# TX_test.net
KiCad netlist of a schematic drawn in EAGLE
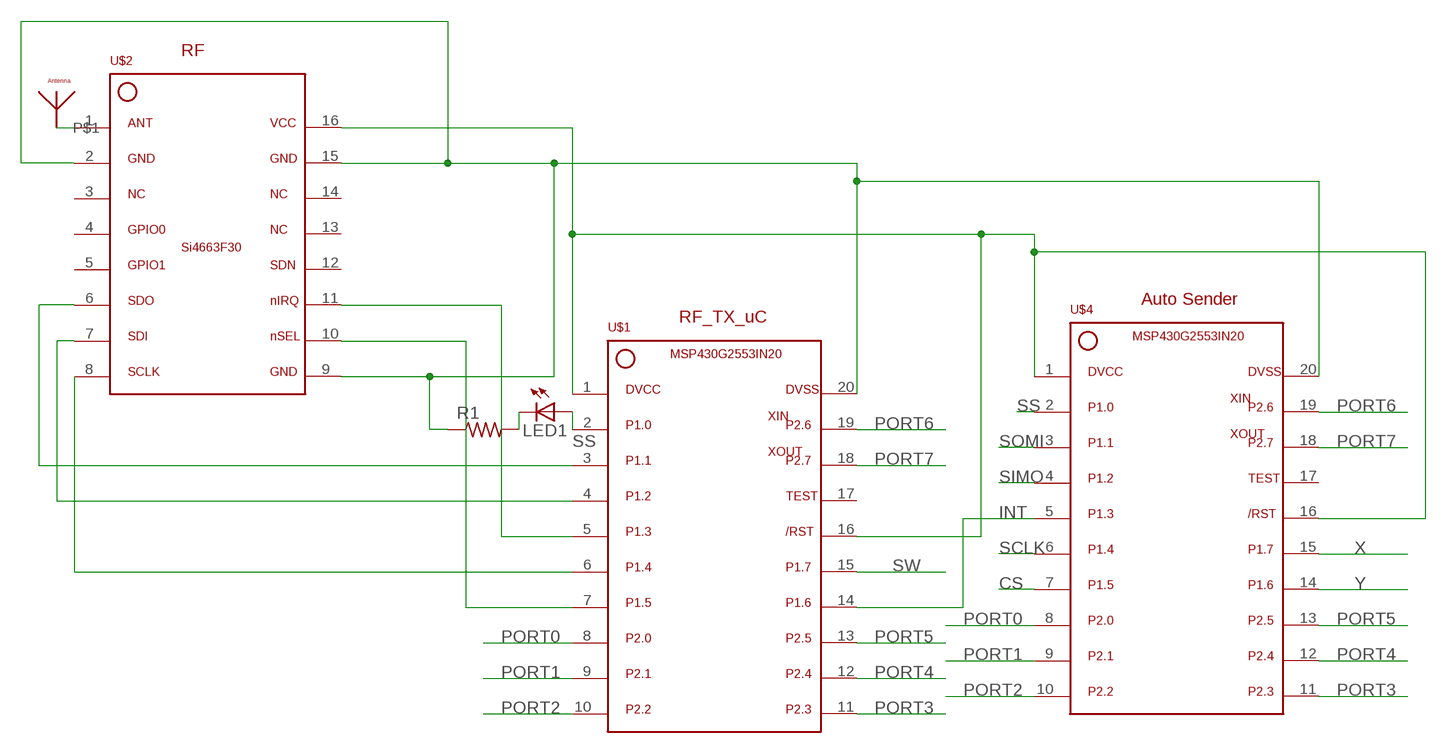
[diagram p0: schematic, sheet 1]

(export (version "E")
  (design (tool "Eeschema 10.0.6"))
  (components
    (comp (ref "LED1")
      (value "LED3MM")
      (footprint "eagle-import:LED3MM")
      (libsource (lib "eagle-import") (part "LED3MM"))
    )
    (comp (ref "R1")
      (value "R-US_0204/7")
      (footprint "eagle-import:0204_7")
      (libsource (lib "eagle-import") (part "R-US_0204/7"))
    )
    (comp (ref "U$1")
      (value "MSP430G2553IN20")
      (footprint "eagle-import:DIP762W53P254L2215H508Q20B")
      (libsource (lib "eagle-import") (part "MSP430G2553IN20"))
    )
    (comp (ref "U$2")
      (value "SI4663F30SI4663F30-3D")
      (footprint "eagle-import:INDCAV400P3800X2000X400-16N")
      (libsource (lib "eagle-import") (part "SI4663F30SI4663F30-3D"))
    )
    (comp (ref "U$3")
      (value "ANTENNA")
      (footprint "eagle-import:ANTENNA")
      (libsource (lib "eagle-import") (part "ANTENNA"))
    )
    (comp (ref "U$4")
      (value "MSP430G2553IN20")
      (footprint "eagle-import:DIP762W53P254L2215H508Q20B")
      (libsource (lib "eagle-import") (part "MSP430G2553IN20"))
    )
  )
  (nets
    (net (code "1") (name "/CS") (class "Default")
      (node (ref "U$4") (pin "7") (pinfunction "P$7_7") (pintype "bidirectional"))
    )
    (net (code "2") (name "/INT") (class "Default")
      (node (ref "U$1") (pin "14") (pinfunction "P$14_14") (pintype "bidirectional"))
      (node (ref "U$4") (pin "5") (pinfunction "P$5_5") (pintype "bidirectional"))
    )
    (net (code "3") (name "/PORT0") (class "Default")
      (node (ref "U$1") (pin "8") (pinfunction "P$8_8") (pintype "bidirectional"))
      (node (ref "U$4") (pin "8") (pinfunction "P$8_8") (pintype "bidirectional"))
    )
    (net (code "4") (name "/PORT1") (class "Default")
      (node (ref "U$1") (pin "9") (pinfunction "P$9_9") (pintype "bidirectional"))
      (node (ref "U$4") (pin "9") (pinfunction "P$9_9") (pintype "bidirectional"))
    )
    (net (code "5") (name "/PORT2") (class "Default")
      (node (ref "U$1") (pin "10") (pinfunction "P$10_10") (pintype "bidirectional"))
      (node (ref "U$4") (pin "10") (pinfunction "P$10_10") (pintype "bidirectional"))
    )
    (net (code "6") (name "/PORT3") (class "Default")
      (node (ref "U$1") (pin "11") (pinfunction "P$11_11") (pintype "bidirectional"))
      (node (ref "U$4") (pin "11") (pinfunction "P$11_11") (pintype "bidirectional"))
    )
    (net (code "7") (name "/PORT4") (class "Default")
      (node (ref "U$1") (pin "12") (pinfunction "P$12_12") (pintype "bidirectional"))
      (node (ref "U$4") (pin "12") (pinfunction "P$12_12") (pintype "bidirectional"))
    )
    (net (code "8") (name "/PORT5") (class "Default")
      (node (ref "U$1") (pin "13") (pinfunction "P$13_13") (pintype "bidirectional"))
      (node (ref "U$4") (pin "13") (pinfunction "P$13_13") (pintype "bidirectional"))
    )
    (net (code "9") (name "/PORT6") (class "Default")
      (node (ref "U$1") (pin "19") (pinfunction "P$19_19") (pintype "bidirectional"))
      (node (ref "U$4") (pin "19") (pinfunction "P$19_19") (pintype "bidirectional"))
    )
    (net (code "10") (name "/PORT7") (class "Default")
      (node (ref "U$1") (pin "18") (pinfunction "P$18_18") (pintype "bidirectional"))
      (node (ref "U$4") (pin "18") (pinfunction "P$18_18") (pintype "bidirectional"))
    )
    (net (code "11") (name "/SCLK") (class "Default")
      (node (ref "U$4") (pin "6") (pinfunction "P$6_6") (pintype "bidirectional"))
    )
    (net (code "12") (name "/SIMO") (class "Default")
      (node (ref "U$4") (pin "4") (pinfunction "P$4_4") (pintype "bidirectional"))
    )
    (net (code "13") (name "/SOMI") (class "Default")
      (node (ref "U$4") (pin "3") (pinfunction "P$3_3") (pintype "bidirectional"))
    )
    (net (code "14") (name "/SS") (class "Default")
      (node (ref "LED1") (pin "A") (pinfunction "A_A") (pintype "passive"))
      (node (ref "U$1") (pin "2") (pinfunction "P$2_2") (pintype "bidirectional"))
      (node (ref "U$4") (pin "2") (pinfunction "P$2_2") (pintype "bidirectional"))
    )
    (net (code "15") (name "/SW") (class "Default")
      (node (ref "U$1") (pin "15") (pinfunction "P$15_15") (pintype "bidirectional"))
    )
    (net (code "16") (name "/X") (class "Default")
      (node (ref "U$4") (pin "15") (pinfunction "P$15_15") (pintype "bidirectional"))
    )
    (net (code "17") (name "/Y") (class "Default")
      (node (ref "U$4") (pin "14") (pinfunction "P$14_14") (pintype "bidirectional"))
    )
    (net (code "18") (name "Net-(LED1-C)") (class "Default")
      (node (ref "LED1") (pin "K") (pinfunction "C_K") (pintype "passive"))
      (node (ref "R1") (pin "2") (pinfunction "2_2") (pintype "passive"))
    )
    (net (code "19") (name "Net-(U$1-P$1)") (class "Default")
      (node (ref "U$1") (pin "1") (pinfunction "P$1_1") (pintype "bidirectional"))
      (node (ref "U$1") (pin "16") (pinfunction "P$16_16") (pintype "bidirectional"))
      (node (ref "U$2") (pin "16") (pinfunction "P$16_16") (pintype "bidirectional"))
      (node (ref "U$4") (pin "1") (pinfunction "P$1_1") (pintype "bidirectional"))
      (node (ref "U$4") (pin "16") (pinfunction "P$16_16") (pintype "bidirectional"))
    )
    (net (code "20") (name "Net-(U$1-P$3)") (class "Default")
      (node (ref "U$1") (pin "3") (pinfunction "P$3_3") (pintype "bidirectional"))
      (node (ref "U$2") (pin "6") (pinfunction "P$6_6") (pintype "bidirectional"))
    )
    (net (code "21") (name "Net-(U$1-P$4)") (class "Default")
      (node (ref "U$1") (pin "4") (pinfunction "P$4_4") (pintype "bidirectional"))
      (node (ref "U$2") (pin "7") (pinfunction "P$7_7") (pintype "bidirectional"))
    )
    (net (code "22") (name "Net-(U$1-P$5)") (class "Default")
      (node (ref "U$1") (pin "5") (pinfunction "P$5_5") (pintype "bidirectional"))
      (node (ref "U$2") (pin "11") (pinfunction "P$11_11") (pintype "bidirectional"))
    )
    (net (code "23") (name "Net-(U$1-P$6)") (class "Default")
      (node (ref "U$1") (pin "6") (pinfunction "P$6_6") (pintype "bidirectional"))
      (node (ref "U$2") (pin "8") (pinfunction "P$8_8") (pintype "bidirectional"))
    )
    (net (code "24") (name "Net-(U$1-P$7)") (class "Default")
      (node (ref "U$1") (pin "7") (pinfunction "P$7_7") (pintype "bidirectional"))
      (node (ref "U$2") (pin "10") (pinfunction "P$10_10") (pintype "bidirectional"))
    )
    (net (code "25") (name "Net-(U$1-P$20)") (class "Default")
      (node (ref "R1") (pin "1") (pinfunction "1_1") (pintype "passive"))
      (node (ref "U$1") (pin "20") (pinfunction "P$20_20") (pintype "bidirectional"))
      (node (ref "U$2") (pin "15") (pinfunction "P$15_15") (pintype "bidirectional"))
      (node (ref "U$2") (pin "2") (pinfunction "P$2_2") (pintype "bidirectional"))
      (node (ref "U$2") (pin "9") (pinfunction "P$9_9") (pintype "bidirectional"))
      (node (ref "U$4") (pin "20") (pinfunction "P$20_20") (pintype "bidirectional"))
    )
    (net (code "26") (name "Net-(U$2-P$1)") (class "Default")
      (node (ref "U$2") (pin "1") (pinfunction "P$1_1") (pintype "bidirectional"))
      (node (ref "U$3") (pin "P$1") (pinfunction "P$1_P$1") (pintype "bidirectional"))
    )
    (net (code "27") (name "unconnected-(U$1-P$17-Pad17)") (class "Default")
      (node (ref "U$1") (pin "17") (pinfunction "P$17_17") (pintype "bidirectional"))
    )
    (net (code "28") (name "unconnected-(U$2-P$3-Pad3)") (class "Default")
      (node (ref "U$2") (pin "3") (pinfunction "P$3_3") (pintype "bidirectional"))
    )
    (net (code "29") (name "unconnected-(U$2-P$4-Pad4)") (class "Default")
      (node (ref "U$2") (pin "4") (pinfunction "P$4_4") (pintype "bidirectional"))
    )
    (net (code "30") (name "unconnected-(U$2-P$5-Pad5)") (class "Default")
      (node (ref "U$2") (pin "5") (pinfunction "P$5_5") (pintype "bidirectional"))
    )
    (net (code "31") (name "unconnected-(U$2-P$12-Pad12)") (class "Default")
      (node (ref "U$2") (pin "12") (pinfunction "P$12_12") (pintype "bidirectional"))
    )
    (net (code "32") (name "unconnected-(U$2-P$13-Pad13)") (class "Default")
      (node (ref "U$2") (pin "13") (pinfunction "P$13_13") (pintype "bidirectional"))
    )
    (net (code "33") (name "unconnected-(U$2-P$14-Pad14)") (class "Default")
      (node (ref "U$2") (pin "14") (pinfunction "P$14_14") (pintype "bidirectional"))
    )
    (net (code "34") (name "unconnected-(U$4-P$17-Pad17)") (class "Default")
      (node (ref "U$4") (pin "17") (pinfunction "P$17_17") (pintype "bidirectional"))
    )
  )
)
